# Kasli-SOC_QUAD_BUCK.net
KiCad netlist of a schematic drawn in Altium Designer
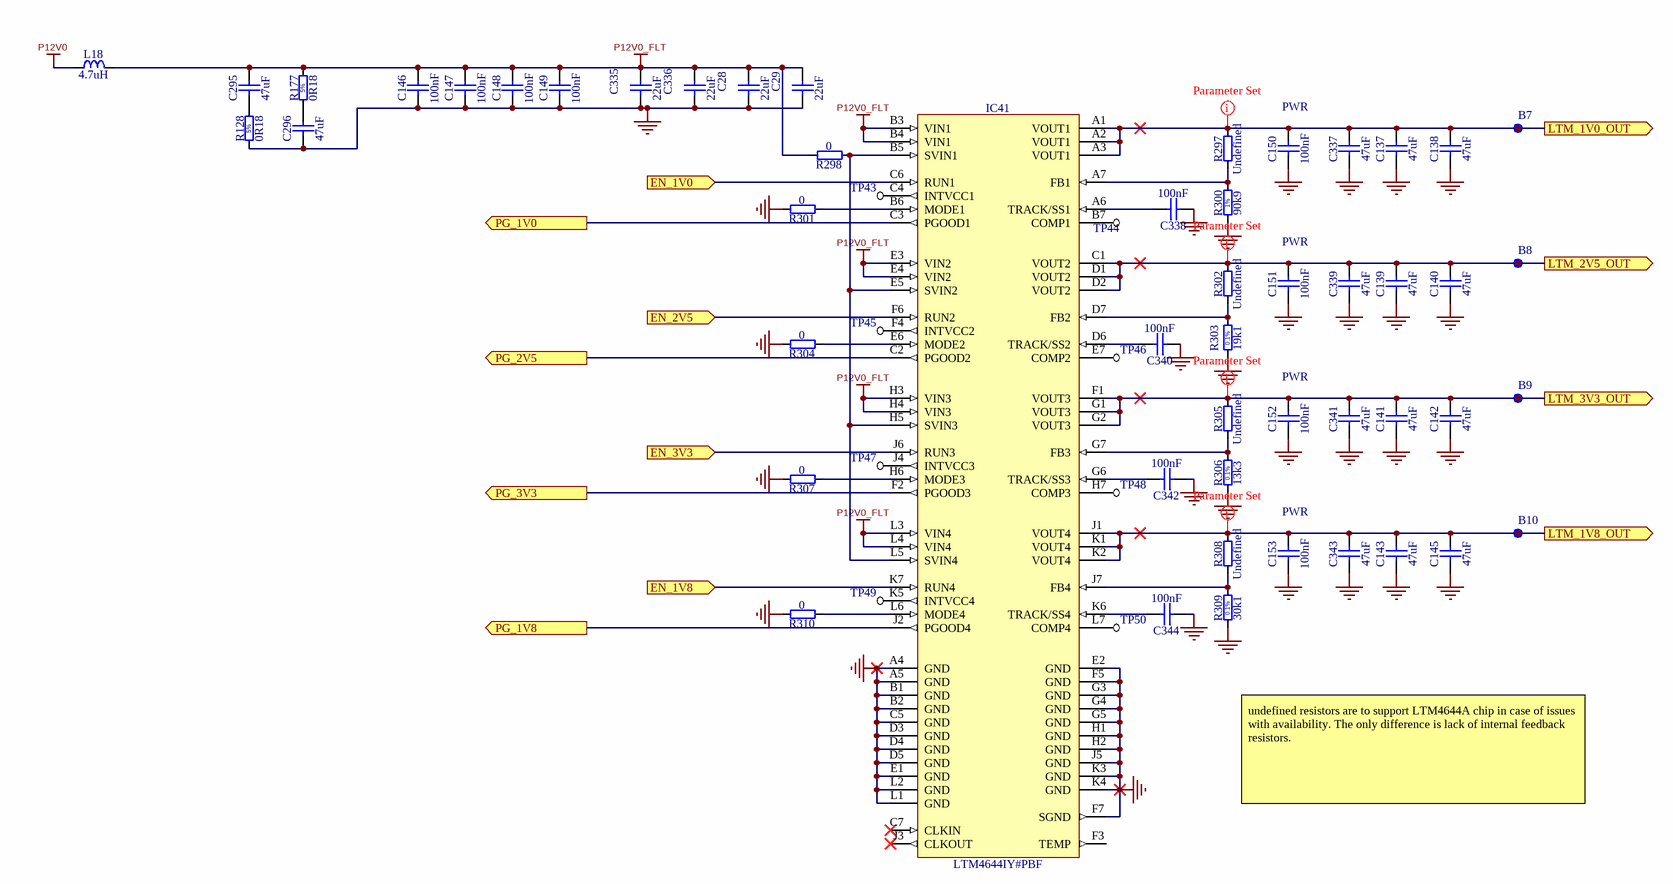
[diagram p0: Kasli-SOC_QUAD_BUCK.SchDoc]

(export (version "E")
  (design (tool "Eeschema 10.0.6"))
  (components
    (comp (ref "B7")
      (value "SMD Pad")
      (footprint "C75")
      (description "Through Hole Pad")
      (fields (field (name "PART NUMBER") "SMD_PAD_D0.75MM") (field (name "AUTHOR") "CERN DEM BC"))
      (libsource (lib "Eletro-mechanical") (part "Single SMD Pad (Round)"))
    )
    (comp (ref "B8")
      (value "SMD Pad")
      (footprint "C75")
      (description "Through Hole Pad")
      (fields (field (name "PART NUMBER") "SMD_PAD_D0.75MM") (field (name "AUTHOR") "CERN DEM BC"))
      (libsource (lib "Eletro-mechanical") (part "Single SMD Pad (Round)"))
    )
    (comp (ref "B9")
      (value "SMD Pad")
      (footprint "C75")
      (description "Through Hole Pad")
      (fields (field (name "PART NUMBER") "SMD_PAD_D0.75MM") (field (name "AUTHOR") "CERN DEM BC"))
      (libsource (lib "Eletro-mechanical") (part "Single SMD Pad (Round)"))
    )
    (comp (ref "B10")
      (value "SMD Pad")
      (footprint "C75")
      (description "Through Hole Pad")
      (fields (field (name "PART NUMBER") "SMD_PAD_D0.75MM") (field (name "AUTHOR") "CERN DEM BC"))
      (libsource (lib "Eletro-mechanical") (part "Single SMD Pad (Round)"))
    )
    (comp (ref "C28")
      (value "22uF")
      (footprint "CAPC2012X135N")
      (description "Non-polarised capacitor")
      (fields
        (field (name "MANUFACTURER PART NUMBER") "CC0805_22UF_16V_10%_X5R")
        (field (name "MANUFACTURER") "GENERIC")
        (field (name "AUTHOR") "CERN DEM JLC")
      )
      (libsource (lib "Capacitors") (part "Capacitor - non polarized"))
    )
    (comp (ref "C29")
      (value "22uF")
      (footprint "CAPC2012X135N")
      (description "Non-polarised capacitor")
      (fields
        (field (name "MANUFACTURER PART NUMBER") "CC0805_22UF_16V_10%_X5R")
        (field (name "MANUFACTURER") "GENERIC")
        (field (name "AUTHOR") "CERN DEM JLC")
      )
      (libsource (lib "Capacitors") (part "Capacitor - non polarized"))
    )
    (comp (ref "C137")
      (value "47uF")
      (footprint "CAPC2012X140N")
      (description "Non-polarised capacitor")
      (fields
        (field (name "MANUFACTURER PART NUMBER") "CC0805_47UF_6.3V_20%_X5R")
        (field (name "MANUFACTURER") "GENERIC")
        (field (name "AUTHOR") "CERN DEM JLC")
      )
      (libsource (lib "Capacitors") (part "Capacitor - non polarized"))
    )
    (comp (ref "C138")
      (value "47uF")
      (footprint "CAPC2012X140N")
      (description "Non-polarised capacitor")
      (fields
        (field (name "MANUFACTURER PART NUMBER") "CC0805_47UF_6.3V_20%_X5R")
        (field (name "MANUFACTURER") "GENERIC")
        (field (name "AUTHOR") "CERN DEM JLC")
      )
      (libsource (lib "Capacitors") (part "Capacitor - non polarized"))
    )
    (comp (ref "C139")
      (value "47uF")
      (footprint "CAPC2012X140N")
      (description "Non-polarised capacitor")
      (fields
        (field (name "MANUFACTURER PART NUMBER") "CC0805_47UF_6.3V_20%_X5R")
        (field (name "MANUFACTURER") "GENERIC")
        (field (name "AUTHOR") "CERN DEM JLC")
      )
      (libsource (lib "Capacitors") (part "Capacitor - non polarized"))
    )
    (comp (ref "C140")
      (value "47uF")
      (footprint "CAPC2012X140N")
      (description "Non-polarised capacitor")
      (fields
        (field (name "MANUFACTURER PART NUMBER") "CC0805_47UF_6.3V_20%_X5R")
        (field (name "MANUFACTURER") "GENERIC")
        (field (name "AUTHOR") "CERN DEM JLC")
      )
      (libsource (lib "Capacitors") (part "Capacitor - non polarized"))
    )
    (comp (ref "C141")
      (value "47uF")
      (footprint "CAPC2012X140N")
      (description "Non-polarised capacitor")
      (fields
        (field (name "MANUFACTURER PART NUMBER") "CC0805_47UF_6.3V_20%_X5R")
        (field (name "MANUFACTURER") "GENERIC")
        (field (name "AUTHOR") "CERN DEM JLC")
      )
      (libsource (lib "Capacitors") (part "Capacitor - non polarized"))
    )
    (comp (ref "C142")
      (value "47uF")
      (footprint "CAPC2012X140N")
      (description "Non-polarised capacitor")
      (fields
        (field (name "MANUFACTURER PART NUMBER") "CC0805_47UF_6.3V_20%_X5R")
        (field (name "MANUFACTURER") "GENERIC")
        (field (name "AUTHOR") "CERN DEM JLC")
      )
      (libsource (lib "Capacitors") (part "Capacitor - non polarized"))
    )
    (comp (ref "C143")
      (value "47uF")
      (footprint "CAPC2012X140N")
      (description "Non-polarised capacitor")
      (fields
        (field (name "MANUFACTURER PART NUMBER") "CC0805_47UF_6.3V_20%_X5R")
        (field (name "MANUFACTURER") "GENERIC")
        (field (name "AUTHOR") "CERN DEM JLC")
      )
      (libsource (lib "Capacitors") (part "Capacitor - non polarized"))
    )
    (comp (ref "C145")
      (value "47uF")
      (footprint "CAPC2012X140N")
      (description "Non-polarised capacitor")
      (fields
        (field (name "MANUFACTURER PART NUMBER") "CC0805_47UF_6.3V_20%_X5R")
        (field (name "MANUFACTURER") "GENERIC")
        (field (name "AUTHOR") "CERN DEM JLC")
      )
      (libsource (lib "Capacitors") (part "Capacitor - non polarized"))
    )
    (comp (ref "C146")
      (value "100nF")
      (footprint "CAPC1005X55N")
      (description "Non-polarised capacitor")
      (fields
        (field (name "PART NUMBER") "CC0402_100NF_16V_10%_X7R")
        (field (name "VOLTAGE") "16V")
        (field (name "AUTHOR") "CERN DEM JLC")
      )
      (libsource (lib "Capacitors") (part "Capacitor - non polarized"))
    )
    (comp (ref "C147")
      (value "100nF")
      (footprint "CAPC1005X55N")
      (description "Non-polarised capacitor")
      (fields
        (field (name "PART NUMBER") "CC0402_100NF_16V_10%_X7R")
        (field (name "VOLTAGE") "16V")
        (field (name "AUTHOR") "CERN DEM JLC")
      )
      (libsource (lib "Capacitors") (part "Capacitor - non polarized"))
    )
    (comp (ref "C148")
      (value "100nF")
      (footprint "CAPC1005X55N")
      (description "Non-polarised capacitor")
      (fields
        (field (name "PART NUMBER") "CC0402_100NF_16V_10%_X7R")
        (field (name "VOLTAGE") "16V")
        (field (name "AUTHOR") "CERN DEM JLC")
      )
      (libsource (lib "Capacitors") (part "Capacitor - non polarized"))
    )
    (comp (ref "C149")
      (value "100nF")
      (footprint "CAPC1005X55N")
      (description "Non-polarised capacitor")
      (fields
        (field (name "PART NUMBER") "CC0402_100NF_16V_10%_X7R")
        (field (name "VOLTAGE") "16V")
        (field (name "AUTHOR") "CERN DEM JLC")
      )
      (libsource (lib "Capacitors") (part "Capacitor - non polarized"))
    )
    (comp (ref "C150")
      (value "100nF")
      (footprint "CAPC1005X55N")
      (description "Non-polarised capacitor")
      (fields
        (field (name "PART NUMBER") "CC0402_100NF_16V_10%_X7R")
        (field (name "VOLTAGE") "16V")
        (field (name "AUTHOR") "CERN DEM JLC")
      )
      (libsource (lib "Capacitors") (part "Capacitor - non polarized"))
    )
    (comp (ref "C151")
      (value "100nF")
      (footprint "CAPC1005X55N")
      (description "Non-polarised capacitor")
      (fields
        (field (name "PART NUMBER") "CC0402_100NF_16V_10%_X7R")
        (field (name "VOLTAGE") "16V")
        (field (name "AUTHOR") "CERN DEM JLC")
      )
      (libsource (lib "Capacitors") (part "Capacitor - non polarized"))
    )
    (comp (ref "C152")
      (value "100nF")
      (footprint "CAPC1005X55N")
      (description "Non-polarised capacitor")
      (fields
        (field (name "PART NUMBER") "CC0402_100NF_16V_10%_X7R")
        (field (name "VOLTAGE") "16V")
        (field (name "AUTHOR") "CERN DEM JLC")
      )
      (libsource (lib "Capacitors") (part "Capacitor - non polarized"))
    )
    (comp (ref "C153")
      (value "100nF")
      (footprint "CAPC1005X55N")
      (description "Non-polarised capacitor")
      (fields
        (field (name "PART NUMBER") "CC0402_100NF_16V_10%_X7R")
        (field (name "VOLTAGE") "16V")
        (field (name "AUTHOR") "CERN DEM JLC")
      )
      (libsource (lib "Capacitors") (part "Capacitor - non polarized"))
    )
    (comp (ref "C295")
      (value "47uF")
      (footprint "CAPC5750X200N")
      (description "Non-polarised capacitor")
      (fields
        (field (name "PART NUMBER") "CC2220_47UF_16V_20%_X7R")
        (field (name "VOLTAGE") "16V")
        (field (name "AUTHOR") "CERN DEM JLC")
      )
      (libsource (lib "Capacitors") (part "Capacitor - non polarized"))
    )
    (comp (ref "C296")
      (value "47uF")
      (footprint "CAPC5750X200N")
      (description "Non-polarised capacitor")
      (fields
        (field (name "PART NUMBER") "CC2220_47UF_16V_20%_X7R")
        (field (name "VOLTAGE") "16V")
        (field (name "AUTHOR") "CERN DEM JLC")
      )
      (libsource (lib "Capacitors") (part "Capacitor - non polarized"))
    )
    (comp (ref "C335")
      (value "22uF")
      (footprint "CAPC2012X135N")
      (description "Non-polarised capacitor")
      (fields
        (field (name "MANUFACTURER PART NUMBER") "CC0805_22UF_16V_10%_X5R")
        (field (name "MANUFACTURER") "GENERIC")
        (field (name "AUTHOR") "CERN DEM JLC")
      )
      (libsource (lib "Capacitors") (part "Capacitor - non polarized"))
    )
    (comp (ref "C336")
      (value "22uF")
      (footprint "CAPC2012X135N")
      (description "Non-polarised capacitor")
      (fields
        (field (name "MANUFACTURER PART NUMBER") "CC0805_22UF_16V_10%_X5R")
        (field (name "MANUFACTURER") "GENERIC")
        (field (name "AUTHOR") "CERN DEM JLC")
      )
      (libsource (lib "Capacitors") (part "Capacitor - non polarized"))
    )
    (comp (ref "C337")
      (value "47uF")
      (footprint "CAPC2012X140N")
      (description "Non-polarised capacitor")
      (fields
        (field (name "MANUFACTURER PART NUMBER") "CC0805_47UF_6.3V_20%_X5R")
        (field (name "MANUFACTURER") "GENERIC")
        (field (name "AUTHOR") "CERN DEM JLC")
      )
      (libsource (lib "Capacitors") (part "Capacitor - non polarized"))
    )
    (comp (ref "C338")
      (value "100nF")
      (footprint "CAPC1005X55N")
      (description "Non-polarised capacitor")
      (fields
        (field (name "PART NUMBER") "CC0402_100NF_16V_10%_X7R")
        (field (name "VOLTAGE") "16V")
        (field (name "AUTHOR") "CERN DEM JLC")
      )
      (libsource (lib "Capacitors") (part "Capacitor - non polarized"))
    )
    (comp (ref "C339")
      (value "47uF")
      (footprint "CAPC2012X140N")
      (description "Non-polarised capacitor")
      (fields
        (field (name "MANUFACTURER PART NUMBER") "CC0805_47UF_6.3V_20%_X5R")
        (field (name "MANUFACTURER") "GENERIC")
        (field (name "AUTHOR") "CERN DEM JLC")
      )
      (libsource (lib "Capacitors") (part "Capacitor - non polarized"))
    )
    (comp (ref "C340")
      (value "100nF")
      (footprint "CAPC1005X55N")
      (description "Non-polarised capacitor")
      (fields
        (field (name "PART NUMBER") "CC0402_100NF_16V_10%_X7R")
        (field (name "VOLTAGE") "16V")
        (field (name "AUTHOR") "CERN DEM JLC")
      )
      (libsource (lib "Capacitors") (part "Capacitor - non polarized"))
    )
    (comp (ref "C341")
      (value "47uF")
      (footprint "CAPC2012X140N")
      (description "Non-polarised capacitor")
      (fields
        (field (name "MANUFACTURER PART NUMBER") "CC0805_47UF_6.3V_20%_X5R")
        (field (name "MANUFACTURER") "GENERIC")
        (field (name "AUTHOR") "CERN DEM JLC")
      )
      (libsource (lib "Capacitors") (part "Capacitor - non polarized"))
    )
    (comp (ref "C342")
      (value "100nF")
      (footprint "CAPC1005X55N")
      (description "Non-polarised capacitor")
      (fields
        (field (name "PART NUMBER") "CC0402_100NF_16V_10%_X7R")
        (field (name "VOLTAGE") "16V")
        (field (name "AUTHOR") "CERN DEM JLC")
      )
      (libsource (lib "Capacitors") (part "Capacitor - non polarized"))
    )
    (comp (ref "C343")
      (value "47uF")
      (footprint "CAPC2012X140N")
      (description "Non-polarised capacitor")
      (fields
        (field (name "MANUFACTURER PART NUMBER") "CC0805_47UF_6.3V_20%_X5R")
        (field (name "MANUFACTURER") "GENERIC")
        (field (name "AUTHOR") "CERN DEM JLC")
      )
      (libsource (lib "Capacitors") (part "Capacitor - non polarized"))
    )
    (comp (ref "C344")
      (value "100nF")
      (footprint "CAPC1005X55N")
      (description "Non-polarised capacitor")
      (fields
        (field (name "PART NUMBER") "CC0402_100NF_16V_10%_X7R")
        (field (name "VOLTAGE") "16V")
        (field (name "AUTHOR") "CERN DEM JLC")
      )
      (libsource (lib "Capacitors") (part "Capacitor - non polarized"))
    )
    (comp (ref "IC41")
      (value "LTM4644IY#PBF")
      (footprint "BGA77C127P7X11_900X1500X521")
      (description "Quad DC/DC µModule Regulator with Configurable 4A Output Array")
      (fields (field (name "MANUFACTURER") "LINEAR TECHNOLOGY") (field (name "AUTHOR") "CERN DEM JLC"))
      (libsource (lib "ICs And Semiconductors") (part "LTM4644"))
    )
    (comp (ref "L18")
      (value "4.7uH")
      (footprint "IND_COOPER_DR74")
      (description "Inductor")
      (fields
        (field (name "PART NUMBER") "IND_4.7UH_20%_COOPER_DR74-4R7-R")
        (field (name "POWER") "3.34A")
        (field (name "AUTHOR") "CERN DEM JLC")
      )
      (libsource (lib "Inductors & Transformers") (part "Inductor"))
    )
    (comp (ref "R128")
      (value "0R18")
      (footprint "RESC2012X70N")
      (description "Resistor - 5%")
      (fields
        (field (name "PART NUMBER") "R0805_0R18_5%_0.25W_250PPM_PANASONIC_ERJ")
        (field (name "POWER") "0.25W")
        (field (name "AUTHOR") "CERN DEM JLC")
      )
      (libsource (lib "Resistors") (part "Resistor - 5%"))
    )
    (comp (ref "R177")
      (value "0R18")
      (footprint "RESC2012X70N")
      (description "Resistor - 5%")
      (fields
        (field (name "PART NUMBER") "R0805_0R18_5%_0.25W_250PPM_PANASONIC_ERJ")
        (field (name "POWER") "0.25W")
        (field (name "AUTHOR") "CERN DEM JLC")
      )
      (libsource (lib "Resistors") (part "Resistor - 5%"))
    )
    (comp (ref "R297")
      (value "Undefined")
      (footprint "RESC1608X55N")
      (description "Resistor")
      (fields (field (name "PART NUMBER") "R0603_NO-VALUE") (field (name "AUTHOR") "CERN DEM JLC"))
      (libsource (lib "Resistors") (part "Resistor"))
    )
    (comp (ref "R298")
      (value "0")
      (footprint "RESC1005X40N")
      (description "Resistor")
      (fields
        (field (name "MANUFACTURER PART NUMBER") "R0402_0R_JUMPER")
        (field (name "MANUFACTURER") "GENERIC")
        (field (name "AUTHOR") "CERN DEM JLC")
      )
      (libsource (lib "Resistors") (part "Resistor"))
    )
    (comp (ref "R300")
      (value "90k9")
      (footprint "RESC1608X55N")
      (description "Resistor - 1%")
      (fields
        (field (name "PART NUMBER") "R0603_90K9_1%_0.1W_100PPM")
        (field (name "POWER") "0.1W")
        (field (name "AUTHOR") "CERN DEM JLC")
      )
      (libsource (lib "Resistors") (part "Resistor - 1%"))
    )
    (comp (ref "R301")
      (value "0")
      (footprint "RESC1005X40N")
      (description "Resistor")
      (fields
        (field (name "MANUFACTURER PART NUMBER") "R0402_0R_JUMPER")
        (field (name "MANUFACTURER") "GENERIC")
        (field (name "AUTHOR") "CERN DEM JLC")
      )
      (libsource (lib "Resistors") (part "Resistor"))
    )
    (comp (ref "R302")
      (value "Undefined")
      (footprint "RESC1608X55N")
      (description "Resistor")
      (fields (field (name "PART NUMBER") "R0603_NO-VALUE") (field (name "AUTHOR") "CERN DEM JLC"))
      (libsource (lib "Resistors") (part "Resistor"))
    )
    (comp (ref "R303")
      (value "19k1")
      (footprint "RESC1608X55N")
      (description "Resistor - 0.1%")
      (fields
        (field (name "PART NUMBER") "R0603_19K1_0.1%_0.063W_10PPM")
        (field (name "POWER") "0.063W")
        (field (name "AUTHOR") "CERN DEM JLC")
      )
      (libsource (lib "Resistors") (part "Resistor - 0.1%"))
    )
    (comp (ref "R304")
      (value "0")
      (footprint "RESC1005X40N")
      (description "Resistor")
      (fields
        (field (name "MANUFACTURER PART NUMBER") "R0402_0R_JUMPER")
        (field (name "MANUFACTURER") "GENERIC")
        (field (name "AUTHOR") "CERN DEM JLC")
      )
      (libsource (lib "Resistors") (part "Resistor"))
    )
    (comp (ref "R305")
      (value "Undefined")
      (footprint "RESC1608X55N")
      (description "Resistor")
      (fields (field (name "PART NUMBER") "R0603_NO-VALUE") (field (name "AUTHOR") "CERN DEM JLC"))
      (libsource (lib "Resistors") (part "Resistor"))
    )
    (comp (ref "R306")
      (value "13k3")
      (footprint "RESC1608X55N")
      (description "Resistor - 0.1%")
      (fields
        (field (name "PART NUMBER") "R0603_13K3_0.1%_0.063W_10PPM")
        (field (name "POWER") "0.063W")
        (field (name "AUTHOR") "CERN DEM JLC")
      )
      (libsource (lib "Resistors") (part "Resistor - 0.1%"))
    )
    (comp (ref "R307")
      (value "0")
      (footprint "RESC1005X40N")
      (description "Resistor")
      (fields
        (field (name "MANUFACTURER PART NUMBER") "R0402_0R_JUMPER")
        (field (name "MANUFACTURER") "GENERIC")
        (field (name "AUTHOR") "CERN DEM JLC")
      )
      (libsource (lib "Resistors") (part "Resistor"))
    )
    (comp (ref "R308")
      (value "Undefined")
      (footprint "RESC1608X55N")
      (description "Resistor")
      (fields (field (name "PART NUMBER") "R0603_NO-VALUE") (field (name "AUTHOR") "CERN DEM JLC"))
      (libsource (lib "Resistors") (part "Resistor"))
    )
    (comp (ref "R309")
      (value "30k1")
      (footprint "RESC1608X55N")
      (description "Resistor - 0.1%")
      (fields
        (field (name "PART NUMBER") "R0603_30K1_0.1%_0.063W_10PPM")
        (field (name "POWER") "0.063W")
        (field (name "AUTHOR") "CERN DEM JLC")
      )
      (libsource (lib "Resistors") (part "Resistor - 0.1%"))
    )
    (comp (ref "R310")
      (value "0")
      (footprint "RESC1005X40N")
      (description "Resistor")
      (fields
        (field (name "MANUFACTURER PART NUMBER") "R0402_0R_JUMPER")
        (field (name "MANUFACTURER") "GENERIC")
        (field (name "AUTHOR") "CERN DEM JLC")
      )
      (libsource (lib "Resistors") (part "Resistor"))
    )
    (comp (ref "TP43")
      (value "TP")
      (footprint "TP")
      (description "Testpoint")
      (libsource (lib "LIBRARY_SCH") (part "TP"))
    )
    (comp (ref "TP44")
      (value "TP")
      (footprint "TP")
      (description "Testpoint")
      (libsource (lib "LIBRARY_SCH") (part "TP"))
    )
    (comp (ref "TP45")
      (value "TP")
      (footprint "TP")
      (description "Testpoint")
      (libsource (lib "LIBRARY_SCH") (part "TP"))
    )
    (comp (ref "TP46")
      (value "TP")
      (footprint "TP")
      (description "Testpoint")
      (libsource (lib "LIBRARY_SCH") (part "TP"))
    )
    (comp (ref "TP47")
      (value "TP")
      (footprint "TP")
      (description "Testpoint")
      (libsource (lib "LIBRARY_SCH") (part "TP"))
    )
    (comp (ref "TP48")
      (value "TP")
      (footprint "TP")
      (description "Testpoint")
      (libsource (lib "LIBRARY_SCH") (part "TP"))
    )
    (comp (ref "TP49")
      (value "TP")
      (footprint "TP")
      (description "Testpoint")
      (libsource (lib "LIBRARY_SCH") (part "TP"))
    )
    (comp (ref "TP50")
      (value "TP")
      (footprint "TP")
      (description "Testpoint")
      (libsource (lib "LIBRARY_SCH") (part "TP"))
    )
  )
  (nets
    (net (code "1") (name "/EN_1V0") (class "Default")
      (node (ref "IC41") (pin "C6") (pinfunction "RUN1_C6") (pintype "input"))
    )
    (net (code "2") (name "/EN_1V8") (class "Default")
      (node (ref "IC41") (pin "K7") (pinfunction "RUN4_K7") (pintype "input"))
    )
    (net (code "3") (name "/EN_2V5") (class "Default")
      (node (ref "IC41") (pin "F6") (pinfunction "RUN2_F6") (pintype "input"))
    )
    (net (code "4") (name "/EN_3V3") (class "Default")
      (node (ref "IC41") (pin "J6") (pinfunction "RUN3_J6") (pintype "input"))
    )
    (net (code "5") (name "/LTM_1V0_OUT") (class "Default")
      (node (ref "B7") (pin "1") (pinfunction "1_1") (pintype "bidirectional"))
      (node (ref "C137") (pin "2") (pinfunction "2_2") (pintype "passive"))
      (node (ref "C138") (pin "2") (pinfunction "2_2") (pintype "passive"))
      (node (ref "C150") (pin "2") (pinfunction "2_2") (pintype "passive"))
      (node (ref "C337") (pin "2") (pinfunction "2_2") (pintype "passive"))
      (node (ref "IC41") (pin "A1") (pinfunction "VOUT1_A1") (pintype "power_in"))
      (node (ref "IC41") (pin "A2") (pinfunction "VOUT1_A2") (pintype "power_in"))
      (node (ref "IC41") (pin "A3") (pinfunction "VOUT1_A3") (pintype "power_in"))
      (node (ref "R297") (pin "2") (pinfunction "2_2") (pintype "passive"))
    )
    (net (code "6") (name "/LTM_1V8_OUT") (class "Default")
      (node (ref "B10") (pin "1") (pinfunction "1_1") (pintype "bidirectional"))
      (node (ref "C143") (pin "2") (pinfunction "2_2") (pintype "passive"))
      (node (ref "C145") (pin "2") (pinfunction "2_2") (pintype "passive"))
      (node (ref "C153") (pin "2") (pinfunction "2_2") (pintype "passive"))
      (node (ref "C343") (pin "2") (pinfunction "2_2") (pintype "passive"))
      (node (ref "IC41") (pin "J1") (pinfunction "VOUT4_J1") (pintype "power_in"))
      (node (ref "IC41") (pin "K1") (pinfunction "VOUT4_K1") (pintype "power_in"))
      (node (ref "IC41") (pin "K2") (pinfunction "VOUT4_K2") (pintype "power_in"))
      (node (ref "R308") (pin "2") (pinfunction "2_2") (pintype "passive"))
    )
    (net (code "7") (name "/LTM_2V5_OUT") (class "Default")
      (node (ref "B8") (pin "1") (pinfunction "1_1") (pintype "bidirectional"))
      (node (ref "C139") (pin "2") (pinfunction "2_2") (pintype "passive"))
      (node (ref "C140") (pin "2") (pinfunction "2_2") (pintype "passive"))
      (node (ref "C151") (pin "2") (pinfunction "2_2") (pintype "passive"))
      (node (ref "C339") (pin "2") (pinfunction "2_2") (pintype "passive"))
      (node (ref "IC41") (pin "C1") (pinfunction "VOUT2_C1") (pintype "power_in"))
      (node (ref "IC41") (pin "D1") (pinfunction "VOUT2_D1") (pintype "power_in"))
      (node (ref "IC41") (pin "D2") (pinfunction "VOUT2_D2") (pintype "power_in"))
      (node (ref "R302") (pin "2") (pinfunction "2_2") (pintype "passive"))
    )
    (net (code "8") (name "/LTM_3V3_OUT") (class "Default")
      (node (ref "B9") (pin "1") (pinfunction "1_1") (pintype "bidirectional"))
      (node (ref "C141") (pin "2") (pinfunction "2_2") (pintype "passive"))
      (node (ref "C142") (pin "2") (pinfunction "2_2") (pintype "passive"))
      (node (ref "C152") (pin "2") (pinfunction "2_2") (pintype "passive"))
      (node (ref "C341") (pin "2") (pinfunction "2_2") (pintype "passive"))
      (node (ref "IC41") (pin "F1") (pinfunction "VOUT3_F1") (pintype "power_in"))
      (node (ref "IC41") (pin "G1") (pinfunction "VOUT3_G1") (pintype "power_in"))
      (node (ref "IC41") (pin "G2") (pinfunction "VOUT3_G2") (pintype "power_in"))
      (node (ref "R305") (pin "2") (pinfunction "2_2") (pintype "passive"))
    )
    (net (code "9") (name "/PG_1V0") (class "Default")
      (node (ref "IC41") (pin "C3") (pinfunction "PGOOD1_C3") (pintype "output"))
    )
    (net (code "10") (name "/PG_1V8") (class "Default")
      (node (ref "IC41") (pin "J2") (pinfunction "PGOOD4_J2") (pintype "output"))
    )
    (net (code "11") (name "/PG_2V5") (class "Default")
      (node (ref "IC41") (pin "C2") (pinfunction "PGOOD2_C2") (pintype "output"))
    )
    (net (code "12") (name "/PG_3V3") (class "Default")
      (node (ref "IC41") (pin "F2") (pinfunction "PGOOD3_F2") (pintype "output"))
    )
    (net (code "13") (name "GND") (class "Default")
      (node (ref "C137") (pin "1") (pinfunction "1_1") (pintype "passive"))
      (node (ref "C138") (pin "1") (pinfunction "1_1") (pintype "passive"))
      (node (ref "C139") (pin "1") (pinfunction "1_1") (pintype "passive"))
      (node (ref "C140") (pin "1") (pinfunction "1_1") (pintype "passive"))
      (node (ref "C141") (pin "1") (pinfunction "1_1") (pintype "passive"))
      (node (ref "C142") (pin "1") (pinfunction "1_1") (pintype "passive"))
      (node (ref "C143") (pin "1") (pinfunction "1_1") (pintype "passive"))
      (node (ref "C145") (pin "1") (pinfunction "1_1") (pintype "passive"))
      (node (ref "C146") (pin "1") (pinfunction "1_1") (pintype "passive"))
      (node (ref "C147") (pin "1") (pinfunction "1_1") (pintype "passive"))
      (node (ref "C148") (pin "1") (pinfunction "1_1") (pintype "passive"))
      (node (ref "C149") (pin "1") (pinfunction "1_1") (pintype "passive"))
      (node (ref "C150") (pin "1") (pinfunction "1_1") (pintype "passive"))
      (node (ref "C151") (pin "1") (pinfunction "1_1") (pintype "passive"))
      (node (ref "C152") (pin "1") (pinfunction "1_1") (pintype "passive"))
      (node (ref "C153") (pin "1") (pinfunction "1_1") (pintype "passive"))
      (node (ref "C28") (pin "1") (pinfunction "1_1") (pintype "passive"))
      (node (ref "C29") (pin "1") (pinfunction "1_1") (pintype "passive"))
      (node (ref "C296") (pin "1") (pinfunction "1_1") (pintype "passive"))
      (node (ref "C335") (pin "1") (pinfunction "1_1") (pintype "passive"))
      (node (ref "C336") (pin "1") (pinfunction "1_1") (pintype "passive"))
      (node (ref "C337") (pin "1") (pinfunction "1_1") (pintype "passive"))
      (node (ref "C338") (pin "1") (pinfunction "1_1") (pintype "passive"))
      (node (ref "C339") (pin "1") (pinfunction "1_1") (pintype "passive"))
      (node (ref "C340") (pin "1") (pinfunction "1_1") (pintype "passive"))
      (node (ref "C341") (pin "1") (pinfunction "1_1") (pintype "passive"))
      (node (ref "C342") (pin "1") (pinfunction "1_1") (pintype "passive"))
      (node (ref "C343") (pin "1") (pinfunction "1_1") (pintype "passive"))
      (node (ref "C344") (pin "1") (pinfunction "1_1") (pintype "passive"))
      (node (ref "IC41") (pin "A4") (pinfunction "GND_A4") (pintype "power_in"))
      (node (ref "IC41") (pin "A5") (pinfunction "GND_A5") (pintype "power_in"))
      (node (ref "IC41") (pin "B1") (pinfunction "GND_B1") (pintype "power_in"))
      (node (ref "IC41") (pin "B2") (pinfunction "GND_B2") (pintype "power_in"))
      (node (ref "IC41") (pin "C5") (pinfunction "GND_C5") (pintype "power_in"))
      (node (ref "IC41") (pin "D3") (pinfunction "GND_D3") (pintype "power_in"))
      (node (ref "IC41") (pin "D4") (pinfunction "GND_D4") (pintype "power_in"))
      (node (ref "IC41") (pin "D5") (pinfunction "GND_D5") (pintype "power_in"))
      (node (ref "IC41") (pin "E1") (pinfunction "GND_E1") (pintype "power_in"))
      (node (ref "IC41") (pin "E2") (pinfunction "GND_E2") (pintype "power_in"))
      (node (ref "IC41") (pin "F5") (pinfunction "GND_F5") (pintype "power_in"))
      (node (ref "IC41") (pin "F7") (pinfunction "SGND_F7") (pintype "output"))
      (node (ref "IC41") (pin "G3") (pinfunction "GND_G3") (pintype "power_in"))
      (node (ref "IC41") (pin "G4") (pinfunction "GND_G4") (pintype "power_in"))
      (node (ref "IC41") (pin "G5") (pinfunction "GND_G5") (pintype "power_in"))
      (node (ref "IC41") (pin "H1") (pinfunction "GND_H1") (pintype "power_in"))
      (node (ref "IC41") (pin "H2") (pinfunction "GND_H2") (pintype "power_in"))
      (node (ref "IC41") (pin "J5") (pinfunction "GND_J5") (pintype "power_in"))
      (node (ref "IC41") (pin "K3") (pinfunction "GND_K3") (pintype "power_in"))
      (node (ref "IC41") (pin "K4") (pinfunction "GND_K4") (pintype "power_in"))
      (node (ref "IC41") (pin "L1") (pinfunction "GND_L1") (pintype "power_in"))
      (node (ref "IC41") (pin "L2") (pinfunction "GND_L2") (pintype "power_in"))
      (node (ref "R128") (pin "1") (pinfunction "1_1") (pintype "passive"))
      (node (ref "R300") (pin "1") (pinfunction "1_1") (pintype "passive"))
      (node (ref "R301") (pin "2") (pinfunction "2_2") (pintype "passive"))
      (node (ref "R303") (pin "1") (pinfunction "1_1") (pintype "passive"))
      (node (ref "R304") (pin "2") (pinfunction "2_2") (pintype "passive"))
      (node (ref "R306") (pin "1") (pinfunction "1_1") (pintype "passive"))
      (node (ref "R307") (pin "2") (pinfunction "2_2") (pintype "passive"))
      (node (ref "R309") (pin "1") (pinfunction "1_1") (pintype "passive"))
      (node (ref "R310") (pin "2") (pinfunction "2_2") (pintype "passive"))
    )
    (net (code "14") (name "Net-(C295-Pad1)") (class "Default")
      (node (ref "C295") (pin "1") (pinfunction "1_1") (pintype "passive"))
      (node (ref "R128") (pin "2") (pinfunction "2_2") (pintype "passive"))
    )
    (net (code "15") (name "Net-(C296-Pad2)") (class "Default")
      (node (ref "C296") (pin "2") (pinfunction "2_2") (pintype "passive"))
      (node (ref "R177") (pin "1") (pinfunction "1_1") (pintype "passive"))
    )
    (net (code "16") (name "Net-(IC41-COMP1)") (class "Default")
      (node (ref "IC41") (pin "B7") (pinfunction "COMP1_B7") (pintype "passive"))
      (node (ref "TP44") (pin "1") (pintype "passive"))
    )
    (net (code "17") (name "Net-(IC41-COMP2)") (class "Default")
      (node (ref "IC41") (pin "E7") (pinfunction "COMP2_E7") (pintype "passive"))
      (node (ref "TP46") (pin "1") (pintype "passive"))
    )
    (net (code "18") (name "Net-(IC41-COMP3)") (class "Default")
      (node (ref "IC41") (pin "H7") (pinfunction "COMP3_H7") (pintype "passive"))
      (node (ref "TP48") (pin "1") (pintype "passive"))
    )
    (net (code "19") (name "Net-(IC41-COMP4)") (class "Default")
      (node (ref "IC41") (pin "L7") (pinfunction "COMP4_L7") (pintype "passive"))
      (node (ref "TP50") (pin "1") (pintype "passive"))
    )
    (net (code "20") (name "Net-(IC41-FB1)") (class "Default")
      (node (ref "IC41") (pin "A7") (pinfunction "FB1_A7") (pintype "input"))
      (node (ref "R297") (pin "1") (pinfunction "1_1") (pintype "passive"))
      (node (ref "R300") (pin "2") (pinfunction "2_2") (pintype "passive"))
    )
    (net (code "21") (name "Net-(IC41-FB2)") (class "Default")
      (node (ref "IC41") (pin "D7") (pinfunction "FB2_D7") (pintype "input"))
      (node (ref "R302") (pin "1") (pinfunction "1_1") (pintype "passive"))
      (node (ref "R303") (pin "2") (pinfunction "2_2") (pintype "passive"))
    )
    (net (code "22") (name "Net-(IC41-FB3)") (class "Default")
      (node (ref "IC41") (pin "G7") (pinfunction "FB3_G7") (pintype "input"))
      (node (ref "R305") (pin "1") (pinfunction "1_1") (pintype "passive"))
      (node (ref "R306") (pin "2") (pinfunction "2_2") (pintype "passive"))
    )
    (net (code "23") (name "Net-(IC41-FB4)") (class "Default")
      (node (ref "IC41") (pin "J7") (pinfunction "FB4_J7") (pintype "input"))
      (node (ref "R308") (pin "1") (pinfunction "1_1") (pintype "passive"))
      (node (ref "R309") (pin "2") (pinfunction "2_2") (pintype "passive"))
    )
    (net (code "24") (name "Net-(IC41-INTVCC1)") (class "Default")
      (node (ref "IC41") (pin "C4") (pinfunction "INTVCC1_C4") (pintype "output"))
      (node (ref "TP43") (pin "1") (pintype "passive"))
    )
    (net (code "25") (name "Net-(IC41-INTVCC2)") (class "Default")
      (node (ref "IC41") (pin "F4") (pinfunction "INTVCC2_F4") (pintype "output"))
      (node (ref "TP45") (pin "1") (pintype "passive"))
    )
    (net (code "26") (name "Net-(IC41-INTVCC3)") (class "Default")
      (node (ref "IC41") (pin "J4") (pinfunction "INTVCC3_J4") (pintype "output"))
      (node (ref "TP47") (pin "1") (pintype "passive"))
    )
    (net (code "27") (name "Net-(IC41-INTVCC4)") (class "Default")
      (node (ref "IC41") (pin "K5") (pinfunction "INTVCC4_K5") (pintype "output"))
      (node (ref "TP49") (pin "1") (pintype "passive"))
    )
    (net (code "28") (name "Net-(IC41-MODE1)") (class "Default")
      (node (ref "IC41") (pin "B6") (pinfunction "MODE1_B6") (pintype "input"))
      (node (ref "R301") (pin "1") (pinfunction "1_1") (pintype "passive"))
    )
    (net (code "29") (name "Net-(IC41-MODE2)") (class "Default")
      (node (ref "IC41") (pin "E6") (pinfunction "MODE2_E6") (pintype "input"))
      (node (ref "R304") (pin "1") (pinfunction "1_1") (pintype "passive"))
    )
    (net (code "30") (name "Net-(IC41-MODE3)") (class "Default")
      (node (ref "IC41") (pin "H6") (pinfunction "MODE3_H6") (pintype "input"))
      (node (ref "R307") (pin "1") (pinfunction "1_1") (pintype "passive"))
    )
    (net (code "31") (name "Net-(IC41-MODE4)") (class "Default")
      (node (ref "IC41") (pin "L6") (pinfunction "MODE4_L6") (pintype "input"))
      (node (ref "R310") (pin "1") (pinfunction "1_1") (pintype "passive"))
    )
    (net (code "32") (name "Net-(IC41-SVIN1)") (class "Default")
      (node (ref "IC41") (pin "B5") (pinfunction "SVIN1_B5") (pintype "input"))
      (node (ref "IC41") (pin "E5") (pinfunction "SVIN2_E5") (pintype "input"))
      (node (ref "IC41") (pin "H5") (pinfunction "SVIN3_H5") (pintype "input"))
      (node (ref "IC41") (pin "L5") (pinfunction "SVIN4_L5") (pintype "input"))
      (node (ref "R298") (pin "1") (pinfunction "1_1") (pintype "passive"))
    )
    (net (code "33") (name "Net-(IC41-TRACK{slash}SS1)") (class "Default")
      (node (ref "C338") (pin "2") (pinfunction "2_2") (pintype "passive"))
      (node (ref "IC41") (pin "A6") (pinfunction "TRACK/SS1_A6") (pintype "input"))
    )
    (net (code "34") (name "Net-(IC41-TRACK{slash}SS2)") (class "Default")
      (node (ref "C340") (pin "2") (pinfunction "2_2") (pintype "passive"))
      (node (ref "IC41") (pin "D6") (pinfunction "TRACK/SS2_D6") (pintype "input"))
    )
    (net (code "35") (name "Net-(IC41-TRACK{slash}SS3)") (class "Default")
      (node (ref "C342") (pin "2") (pinfunction "2_2") (pintype "passive"))
      (node (ref "IC41") (pin "G6") (pinfunction "TRACK/SS3_G6") (pintype "input"))
    )
    (net (code "36") (name "Net-(IC41-TRACK{slash}SS4)") (class "Default")
      (node (ref "C344") (pin "2") (pinfunction "2_2") (pintype "passive"))
      (node (ref "IC41") (pin "K6") (pinfunction "TRACK/SS4_K6") (pintype "input"))
    )
    (net (code "37") (name "P12V0") (class "Default")
      (node (ref "L18") (pin "1") (pinfunction "1_1") (pintype "passive"))
    )
    (net (code "38") (name "P12V0_FLT") (class "Default")
      (node (ref "C146") (pin "2") (pinfunction "2_2") (pintype "passive"))
      (node (ref "C147") (pin "2") (pinfunction "2_2") (pintype "passive"))
      (node (ref "C148") (pin "2") (pinfunction "2_2") (pintype "passive"))
      (node (ref "C149") (pin "2") (pinfunction "2_2") (pintype "passive"))
      (node (ref "C28") (pin "2") (pinfunction "2_2") (pintype "passive"))
      (node (ref "C29") (pin "2") (pinfunction "2_2") (pintype "passive"))
      (node (ref "C295") (pin "2") (pinfunction "2_2") (pintype "passive"))
      (node (ref "C335") (pin "2") (pinfunction "2_2") (pintype "passive"))
      (node (ref "C336") (pin "2") (pinfunction "2_2") (pintype "passive"))
      (node (ref "IC41") (pin "B3") (pinfunction "VIN1_B3") (pintype "input"))
      (node (ref "IC41") (pin "B4") (pinfunction "VIN1_B4") (pintype "input"))
      (node (ref "IC41") (pin "E3") (pinfunction "VIN2_E3") (pintype "input"))
      (node (ref "IC41") (pin "E4") (pinfunction "VIN2_E4") (pintype "input"))
      (node (ref "IC41") (pin "H3") (pinfunction "VIN3_H3") (pintype "input"))
      (node (ref "IC41") (pin "H4") (pinfunction "VIN3_H4") (pintype "input"))
      (node (ref "IC41") (pin "L3") (pinfunction "VIN4_L3") (pintype "input"))
      (node (ref "IC41") (pin "L4") (pinfunction "VIN4_L4") (pintype "input"))
      (node (ref "L18") (pin "2") (pinfunction "2_2") (pintype "passive"))
      (node (ref "R177") (pin "2") (pinfunction "2_2") (pintype "passive"))
      (node (ref "R298") (pin "2") (pinfunction "2_2") (pintype "passive"))
    )
    (net (code "39") (name "unconnected-(IC41-CLKIN-PadC7)") (class "Default")
      (node (ref "IC41") (pin "C7") (pinfunction "CLKIN_C7") (pintype "input+no_connect"))
    )
    (net (code "40") (name "unconnected-(IC41-CLKOUT-PadJ3)") (class "Default")
      (node (ref "IC41") (pin "J3") (pinfunction "CLKOUT_J3") (pintype "output+no_connect"))
    )
    (net (code "41") (name "unconnected-(IC41-TEMP-PadF3)") (class "Default")
      (node (ref "IC41") (pin "F3") (pinfunction "TEMP_F3") (pintype "output"))
    )
  )
)
